# SMART4RGB.net
KiCad netlist of a schematic drawn in EAGLE
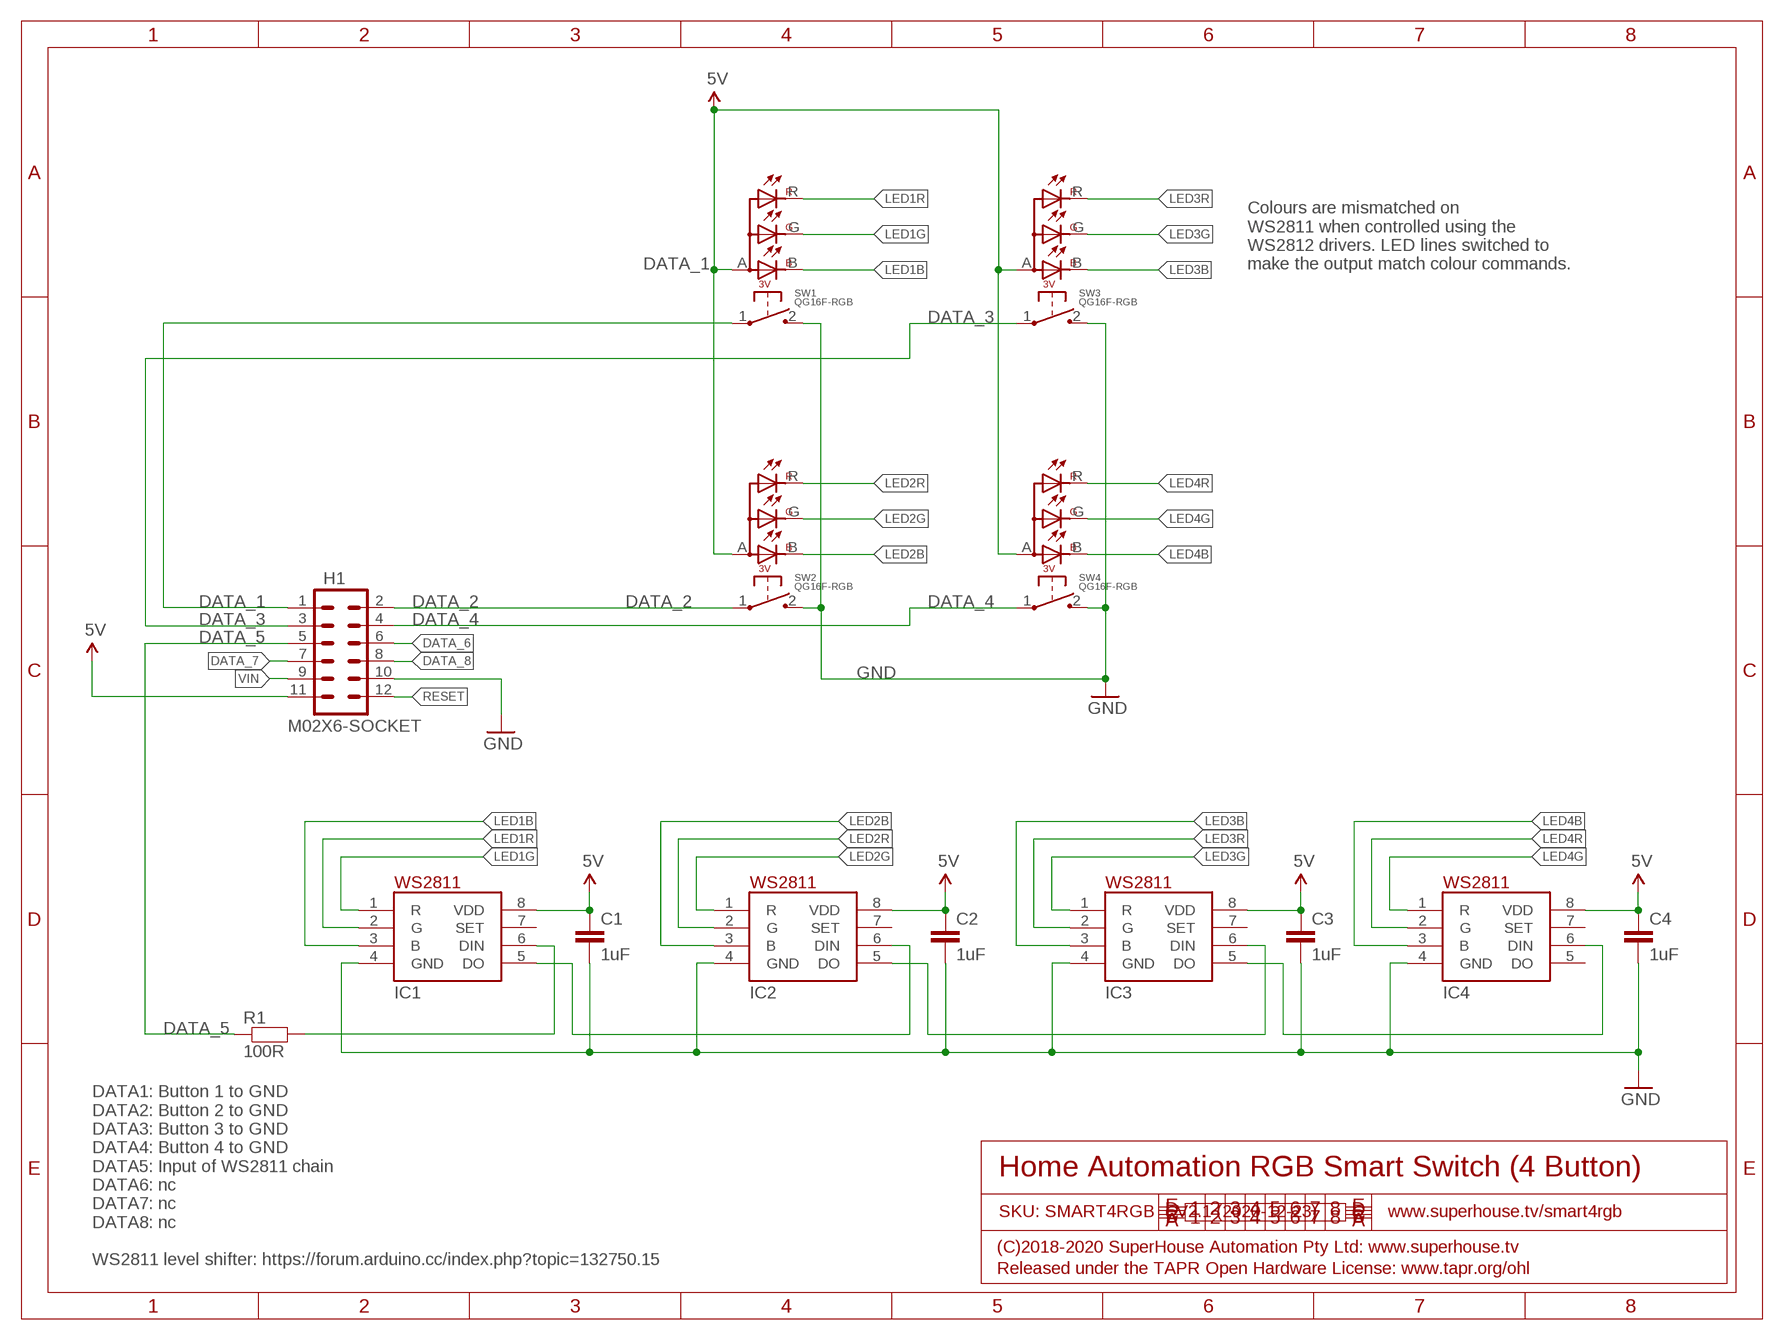
[diagram p0: schematic, sheet 1]

(export (version "E")
  (design (tool "Eeschema 10.0.6"))
  (components
    (comp (ref "C1")
      (value "1uF")
      (footprint "eagle-import:C0603")
      (libsource (lib "eagle-import") (part "CAP0603"))
    )
    (comp (ref "C2")
      (value "1uF")
      (footprint "eagle-import:C0603")
      (libsource (lib "eagle-import") (part "CAP0603"))
    )
    (comp (ref "C3")
      (value "1uF")
      (footprint "eagle-import:C0603")
      (libsource (lib "eagle-import") (part "CAP0603"))
    )
    (comp (ref "C4")
      (value "1uF")
      (footprint "eagle-import:C0603")
      (libsource (lib "eagle-import") (part "CAP0603"))
    )
    (comp (ref "H1")
      (value "M02X6-SOCKET")
      (footprint "eagle-import:2X06-S")
      (libsource (lib "eagle-import") (part "M02X6-SOCKET"))
    )
    (comp (ref "IC1")
      (value "WS2811-SOP8")
      (footprint "eagle-import:SO08-SKINNYPADS")
      (libsource (lib "eagle-import") (part "WS2811-SOP8"))
    )
    (comp (ref "IC2")
      (value "WS2811-SOP8")
      (footprint "eagle-import:SO08-SKINNYPADS")
      (libsource (lib "eagle-import") (part "WS2811-SOP8"))
    )
    (comp (ref "IC3")
      (value "WS2811-SOP8")
      (footprint "eagle-import:SO08-SKINNYPADS")
      (libsource (lib "eagle-import") (part "WS2811-SOP8"))
    )
    (comp (ref "IC4")
      (value "WS2811-SOP8")
      (footprint "eagle-import:SO08-SKINNYPADS")
      (libsource (lib "eagle-import") (part "WS2811-SOP8"))
    )
    (comp (ref "R1")
      (value "100R")
      (footprint "eagle-import:R0603")
      (libsource (lib "eagle-import") (part "RESISTOR0603"))
    )
    (comp (ref "SW1")
      (value "QG16F-RGB")
      (footprint "eagle-import:QG16F-RGB")
      (libsource (lib "eagle-import") (part "QG16F-RGB"))
    )
    (comp (ref "SW2")
      (value "QG16F-RGB")
      (footprint "eagle-import:QG16F-RGB")
      (libsource (lib "eagle-import") (part "QG16F-RGB"))
    )
    (comp (ref "SW3")
      (value "QG16F-RGB")
      (footprint "eagle-import:QG16F-RGB")
      (libsource (lib "eagle-import") (part "QG16F-RGB"))
    )
    (comp (ref "SW4")
      (value "QG16F-RGB")
      (footprint "eagle-import:QG16F-RGB")
      (libsource (lib "eagle-import") (part "QG16F-RGB"))
    )
  )
  (nets
    (net (code "1") (name "/DATA_1") (class "Default")
      (node (ref "H1") (pin "1") (pinfunction "1_1") (pintype "passive"))
      (node (ref "SW1") (pin "1") (pinfunction "1_1") (pintype "passive"))
    )
    (net (code "2") (name "/DATA_2") (class "Default")
      (node (ref "H1") (pin "2") (pinfunction "2_2") (pintype "passive"))
      (node (ref "SW2") (pin "1") (pinfunction "1_1") (pintype "passive"))
    )
    (net (code "3") (name "/DATA_3") (class "Default")
      (node (ref "H1") (pin "3") (pinfunction "3_3") (pintype "passive"))
      (node (ref "SW3") (pin "1") (pinfunction "1_1") (pintype "passive"))
    )
    (net (code "4") (name "/DATA_4") (class "Default")
      (node (ref "H1") (pin "4") (pinfunction "4_4") (pintype "passive"))
      (node (ref "SW4") (pin "1") (pinfunction "1_1") (pintype "passive"))
    )
    (net (code "5") (name "/DATA_5") (class "Default")
      (node (ref "H1") (pin "5") (pinfunction "5_5") (pintype "passive"))
      (node (ref "R1") (pin "1") (pinfunction "1_1") (pintype "passive"))
    )
    (net (code "6") (name "5V") (class "Default")
      (node (ref "C1") (pin "1") (pinfunction "1_1") (pintype "passive"))
      (node (ref "C2") (pin "1") (pinfunction "1_1") (pintype "passive"))
      (node (ref "C3") (pin "1") (pinfunction "1_1") (pintype "passive"))
      (node (ref "C4") (pin "1") (pinfunction "1_1") (pintype "passive"))
      (node (ref "H1") (pin "11") (pinfunction "11_11") (pintype "passive"))
      (node (ref "IC1") (pin "8") (pinfunction "VDD_8") (pintype "power_in"))
      (node (ref "IC2") (pin "8") (pinfunction "VDD_8") (pintype "power_in"))
      (node (ref "IC3") (pin "8") (pinfunction "VDD_8") (pintype "power_in"))
      (node (ref "IC4") (pin "8") (pinfunction "VDD_8") (pintype "power_in"))
      (node (ref "SW1") (pin "A") (pinfunction "+_A") (pintype "passive"))
      (node (ref "SW2") (pin "A") (pinfunction "+_A") (pintype "passive"))
      (node (ref "SW3") (pin "A") (pinfunction "+_A") (pintype "passive"))
      (node (ref "SW4") (pin "A") (pinfunction "+_A") (pintype "passive"))
    )
    (net (code "7") (name "DATA_6") (class "Default")
      (node (ref "H1") (pin "6") (pinfunction "6_6") (pintype "passive"))
    )
    (net (code "8") (name "DATA_7") (class "Default")
      (node (ref "H1") (pin "7") (pinfunction "7_7") (pintype "passive"))
    )
    (net (code "9") (name "DATA_8") (class "Default")
      (node (ref "H1") (pin "8") (pinfunction "8_8") (pintype "passive"))
    )
    (net (code "10") (name "GND") (class "Default")
      (node (ref "C1") (pin "2") (pinfunction "2_2") (pintype "passive"))
      (node (ref "C2") (pin "2") (pinfunction "2_2") (pintype "passive"))
      (node (ref "C3") (pin "2") (pinfunction "2_2") (pintype "passive"))
      (node (ref "C4") (pin "2") (pinfunction "2_2") (pintype "passive"))
      (node (ref "H1") (pin "10") (pinfunction "10_10") (pintype "passive"))
      (node (ref "IC1") (pin "4") (pinfunction "GND_4") (pintype "power_in"))
      (node (ref "IC2") (pin "4") (pinfunction "GND_4") (pintype "power_in"))
      (node (ref "IC3") (pin "4") (pinfunction "GND_4") (pintype "power_in"))
      (node (ref "IC4") (pin "4") (pinfunction "GND_4") (pintype "power_in"))
      (node (ref "SW1") (pin "2") (pinfunction "2_2") (pintype "passive"))
      (node (ref "SW2") (pin "2") (pinfunction "2_2") (pintype "passive"))
      (node (ref "SW3") (pin "2") (pinfunction "2_2") (pintype "passive"))
      (node (ref "SW4") (pin "2") (pinfunction "2_2") (pintype "passive"))
    )
    (net (code "11") (name "LED1B") (class "Default")
      (node (ref "IC1") (pin "3") (pinfunction "B_3") (pintype "open_collector"))
      (node (ref "SW1") (pin "B") (pinfunction "B_B") (pintype "passive"))
    )
    (net (code "12") (name "LED1G") (class "Default")
      (node (ref "IC1") (pin "1") (pinfunction "R_1") (pintype "open_collector"))
      (node (ref "SW1") (pin "G") (pinfunction "G_G") (pintype "passive"))
    )
    (net (code "13") (name "LED1R") (class "Default")
      (node (ref "IC1") (pin "2") (pinfunction "G_2") (pintype "open_collector"))
      (node (ref "SW1") (pin "R") (pinfunction "R_R") (pintype "passive"))
    )
    (net (code "14") (name "LED2B") (class "Default")
      (node (ref "IC2") (pin "3") (pinfunction "B_3") (pintype "open_collector"))
      (node (ref "SW2") (pin "B") (pinfunction "B_B") (pintype "passive"))
    )
    (net (code "15") (name "LED2G") (class "Default")
      (node (ref "IC2") (pin "1") (pinfunction "R_1") (pintype "open_collector"))
      (node (ref "SW2") (pin "G") (pinfunction "G_G") (pintype "passive"))
    )
    (net (code "16") (name "LED2R") (class "Default")
      (node (ref "IC2") (pin "2") (pinfunction "G_2") (pintype "open_collector"))
      (node (ref "SW2") (pin "R") (pinfunction "R_R") (pintype "passive"))
    )
    (net (code "17") (name "LED3B") (class "Default")
      (node (ref "IC3") (pin "3") (pinfunction "B_3") (pintype "open_collector"))
      (node (ref "SW3") (pin "B") (pinfunction "B_B") (pintype "passive"))
    )
    (net (code "18") (name "LED3G") (class "Default")
      (node (ref "IC3") (pin "1") (pinfunction "R_1") (pintype "open_collector"))
      (node (ref "SW3") (pin "G") (pinfunction "G_G") (pintype "passive"))
    )
    (net (code "19") (name "LED3R") (class "Default")
      (node (ref "IC3") (pin "2") (pinfunction "G_2") (pintype "open_collector"))
      (node (ref "SW3") (pin "R") (pinfunction "R_R") (pintype "passive"))
    )
    (net (code "20") (name "LED4B") (class "Default")
      (node (ref "IC4") (pin "3") (pinfunction "B_3") (pintype "open_collector"))
      (node (ref "SW4") (pin "B") (pinfunction "B_B") (pintype "passive"))
    )
    (net (code "21") (name "LED4G") (class "Default")
      (node (ref "IC4") (pin "1") (pinfunction "R_1") (pintype "open_collector"))
      (node (ref "SW4") (pin "G") (pinfunction "G_G") (pintype "passive"))
    )
    (net (code "22") (name "LED4R") (class "Default")
      (node (ref "IC4") (pin "2") (pinfunction "G_2") (pintype "open_collector"))
      (node (ref "SW4") (pin "R") (pinfunction "R_R") (pintype "passive"))
    )
    (net (code "23") (name "Net-(IC1-DIN)") (class "Default")
      (node (ref "IC1") (pin "6") (pinfunction "DIN_6") (pintype "input"))
      (node (ref "R1") (pin "2") (pinfunction "2_2") (pintype "passive"))
    )
    (net (code "24") (name "Net-(IC1-DO)") (class "Default")
      (node (ref "IC1") (pin "5") (pinfunction "DO_5") (pintype "output"))
      (node (ref "IC2") (pin "6") (pinfunction "DIN_6") (pintype "input"))
    )
    (net (code "25") (name "Net-(IC2-DO)") (class "Default")
      (node (ref "IC2") (pin "5") (pinfunction "DO_5") (pintype "output"))
      (node (ref "IC3") (pin "6") (pinfunction "DIN_6") (pintype "input"))
    )
    (net (code "26") (name "Net-(IC3-DO)") (class "Default")
      (node (ref "IC3") (pin "5") (pinfunction "DO_5") (pintype "output"))
      (node (ref "IC4") (pin "6") (pinfunction "DIN_6") (pintype "input"))
    )
    (net (code "27") (name "RESET") (class "Default")
      (node (ref "H1") (pin "12") (pinfunction "12_12") (pintype "passive"))
    )
    (net (code "28") (name "VIN") (class "Default")
      (node (ref "H1") (pin "9") (pinfunction "9_9") (pintype "passive"))
    )
    (net (code "29") (name "unconnected-(IC1-SET-Pad7)") (class "Default")
      (node (ref "IC1") (pin "7") (pinfunction "SET_7") (pintype "input"))
    )
    (net (code "30") (name "unconnected-(IC2-SET-Pad7)") (class "Default")
      (node (ref "IC2") (pin "7") (pinfunction "SET_7") (pintype "input"))
    )
    (net (code "31") (name "unconnected-(IC3-SET-Pad7)") (class "Default")
      (node (ref "IC3") (pin "7") (pinfunction "SET_7") (pintype "input"))
    )
    (net (code "32") (name "unconnected-(IC4-DO-Pad5)") (class "Default")
      (node (ref "IC4") (pin "5") (pinfunction "DO_5") (pintype "output"))
    )
    (net (code "33") (name "unconnected-(IC4-SET-Pad7)") (class "Default")
      (node (ref "IC4") (pin "7") (pinfunction "SET_7") (pintype "input"))
    )
  )
)
